# Boris_IO_3.net
KiCad netlist of a schematic drawn in Altium Designer
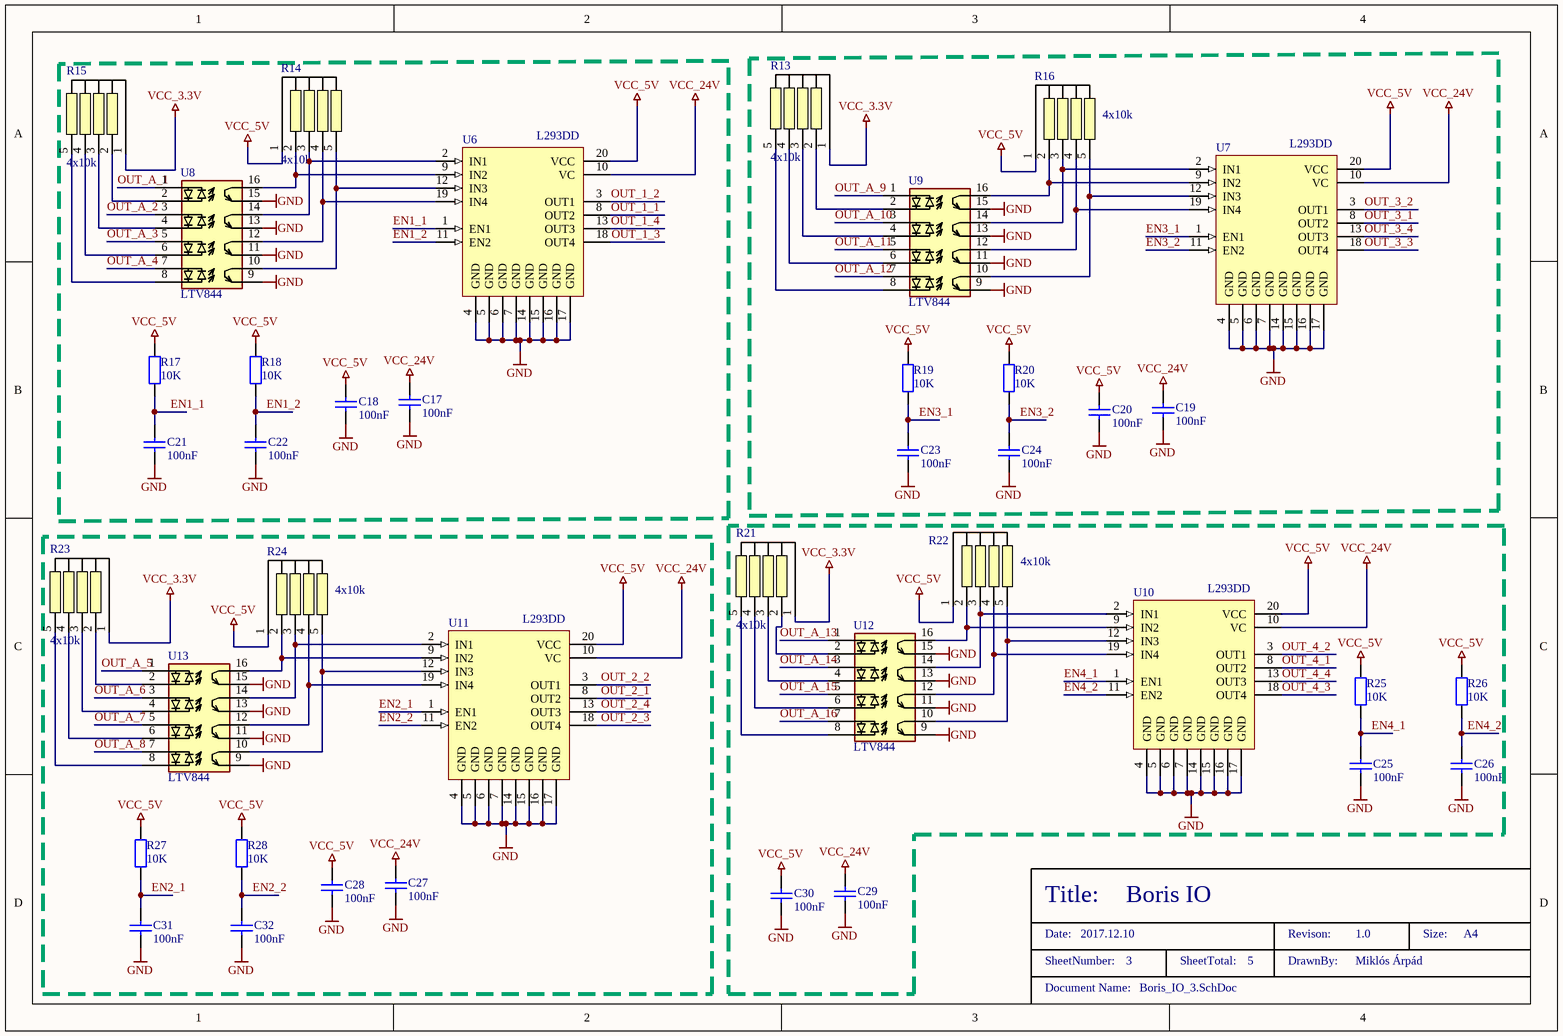
[diagram p0: Boris_IO_3.SchDoc]

(export (version "E")
  (design (tool "Eeschema 10.0.6"))
  (components
    (comp (ref "C17")
      (value "100nF")
      (footprint "0805_CAP")
      (description "Capacitor")
      (libsource (lib "Miscellaneous Devices") (part "Cap"))
    )
    (comp (ref "C18")
      (value "100nF")
      (footprint "0805_CAP")
      (description "Capacitor")
      (libsource (lib "Miscellaneous Devices") (part "Cap"))
    )
    (comp (ref "C19")
      (value "100nF")
      (footprint "0805_CAP")
      (description "Capacitor")
      (libsource (lib "Miscellaneous Devices") (part "Cap"))
    )
    (comp (ref "C20")
      (value "100nF")
      (footprint "0805_CAP")
      (description "Capacitor")
      (libsource (lib "Miscellaneous Devices") (part "Cap"))
    )
    (comp (ref "C21")
      (value "100nF")
      (footprint "0805_CAP")
      (description "Capacitor")
      (libsource (lib "Miscellaneous Devices") (part "Cap"))
    )
    (comp (ref "C22")
      (value "100nF")
      (footprint "0805_CAP")
      (description "Capacitor")
      (libsource (lib "Miscellaneous Devices") (part "Cap"))
    )
    (comp (ref "C23")
      (value "100nF")
      (footprint "0805_CAP")
      (description "Capacitor")
      (libsource (lib "Miscellaneous Devices") (part "Cap"))
    )
    (comp (ref "C24")
      (value "100nF")
      (footprint "0805_CAP")
      (description "Capacitor")
      (libsource (lib "Miscellaneous Devices") (part "Cap"))
    )
    (comp (ref "C25")
      (value "100nF")
      (footprint "0805_CAP")
      (description "Capacitor")
      (libsource (lib "Miscellaneous Devices") (part "Cap"))
    )
    (comp (ref "C26")
      (value "100nF")
      (footprint "0805_CAP")
      (description "Capacitor")
      (libsource (lib "Miscellaneous Devices") (part "Cap"))
    )
    (comp (ref "C27")
      (value "100nF")
      (footprint "0805_CAP")
      (description "Capacitor")
      (libsource (lib "Miscellaneous Devices") (part "Cap"))
    )
    (comp (ref "C28")
      (value "100nF")
      (footprint "0805_CAP")
      (description "Capacitor")
      (libsource (lib "Miscellaneous Devices") (part "Cap"))
    )
    (comp (ref "C29")
      (value "100nF")
      (footprint "0805_CAP")
      (description "Capacitor")
      (libsource (lib "Miscellaneous Devices") (part "Cap"))
    )
    (comp (ref "C30")
      (value "100nF")
      (footprint "0805_CAP")
      (description "Capacitor")
      (libsource (lib "Miscellaneous Devices") (part "Cap"))
    )
    (comp (ref "C31")
      (value "100nF")
      (footprint "0805_CAP")
      (description "Capacitor")
      (libsource (lib "Miscellaneous Devices") (part "Cap"))
    )
    (comp (ref "C32")
      (value "100nF")
      (footprint "0805_CAP")
      (description "Capacitor")
      (libsource (lib "Miscellaneous Devices") (part "Cap"))
    )
    (comp (ref "R13") (value "4x10k") (footprint "NFD_SIL-RES-5") (libsource (lib "") (part "SIL_10k_1")))
    (comp (ref "R14") (value "4x10k") (footprint "NFD_SIL-RES-5") (libsource (lib "IO-01") (part "SIL_10k")))
    (comp (ref "R15") (value "4x10k") (footprint "NFD_SIL-RES-5") (libsource (lib "") (part "SIL_10k_1")))
    (comp (ref "R16") (value "4x10k") (footprint "NFD_SIL-RES-5") (libsource (lib "IO-01") (part "SIL_10k")))
    (comp (ref "R17")
      (value "10K")
      (footprint "0805_RES")
      (description "Resistor")
      (libsource (lib "Miscellaneous Devices") (part "Res2"))
    )
    (comp (ref "R18")
      (value "10K")
      (footprint "0805_RES")
      (description "Resistor")
      (libsource (lib "Miscellaneous Devices") (part "Res2"))
    )
    (comp (ref "R19")
      (value "10K")
      (footprint "0805_RES")
      (description "Resistor")
      (libsource (lib "Miscellaneous Devices") (part "Res2"))
    )
    (comp (ref "R20")
      (value "10K")
      (footprint "0805_RES")
      (description "Resistor")
      (libsource (lib "Miscellaneous Devices") (part "Res2"))
    )
    (comp (ref "R21") (value "4x10k") (footprint "NFD_SIL-RES-5") (libsource (lib "") (part "SIL_10k_1")))
    (comp (ref "R22") (value "4x10k") (footprint "NFD_SIL-RES-5") (libsource (lib "IO-01") (part "SIL_10k")))
    (comp (ref "R23") (value "4x10k") (footprint "NFD_SIL-RES-5") (libsource (lib "") (part "SIL_10k_1")))
    (comp (ref "R24") (value "4x10k") (footprint "NFD_SIL-RES-5") (libsource (lib "IO-01") (part "SIL_10k")))
    (comp (ref "R25")
      (value "10K")
      (footprint "0805_RES")
      (description "Resistor")
      (libsource (lib "Miscellaneous Devices") (part "Res2"))
    )
    (comp (ref "R26")
      (value "10K")
      (footprint "0805_RES")
      (description "Resistor")
      (libsource (lib "Miscellaneous Devices") (part "Res2"))
    )
    (comp (ref "R27")
      (value "10K")
      (footprint "0805_RES")
      (description "Resistor")
      (libsource (lib "Miscellaneous Devices") (part "Res2"))
    )
    (comp (ref "R28")
      (value "10K")
      (footprint "0805_RES")
      (description "Resistor")
      (libsource (lib "Miscellaneous Devices") (part "Res2"))
    )
    (comp (ref "U6")
      (value "L293DD")
      (footprint "SO20_N")
      (description "Push-Pull Four Channel Driver With Diode")
      (fields (field (name "PUBLISHER") "Altium Limited"))
      (libsource (lib "ST Interface DC & Stepper Motor Controller") (part "L293DD"))
    )
    (comp (ref "U7")
      (value "L293DD")
      (footprint "SO20_N")
      (description "Push-Pull Four Channel Driver With Diode")
      (fields (field (name "PUBLISHER") "Altium Limited"))
      (libsource (lib "ST Interface DC & Stepper Motor Controller") (part "L293DD"))
    )
    (comp (ref "U8")
      (value "LTV844")
      (footprint "LTV844S")
      (description "4x optocoupler")
      (libsource (lib "MisiIC1") (part "LTV844"))
    )
    (comp (ref "U9")
      (value "LTV844")
      (footprint "LTV844S")
      (description "4x optocoupler")
      (libsource (lib "MisiIC1") (part "LTV844"))
    )
    (comp (ref "U10")
      (value "L293DD")
      (footprint "SO20_N")
      (description "Push-Pull Four Channel Driver With Diode")
      (fields (field (name "PUBLISHER") "Altium Limited"))
      (libsource (lib "ST Interface DC & Stepper Motor Controller") (part "L293DD"))
    )
    (comp (ref "U11")
      (value "L293DD")
      (footprint "SO20_N")
      (description "Push-Pull Four Channel Driver With Diode")
      (fields (field (name "PUBLISHER") "Altium Limited"))
      (libsource (lib "ST Interface DC & Stepper Motor Controller") (part "L293DD"))
    )
    (comp (ref "U12")
      (value "LTV844")
      (footprint "LTV844S")
      (description "4x optocoupler")
      (libsource (lib "MisiIC1") (part "LTV844"))
    )
    (comp (ref "U13")
      (value "LTV844")
      (footprint "LTV844S")
      (description "4x optocoupler")
      (libsource (lib "MisiIC1") (part "LTV844"))
    )
  )
  (nets
    (net (code "1") (name "/EN1_1") (class "Default")
      (node (ref "C21") (pin "1") (pinfunction "1_1") (pintype "passive"))
      (node (ref "R17") (pin "1") (pinfunction "1_1") (pintype "passive"))
      (node (ref "U6") (pin "1") (pinfunction "EN1_1") (pintype "input"))
    )
    (net (code "2") (name "/EN1_2") (class "Default")
      (node (ref "C22") (pin "1") (pinfunction "1_1") (pintype "passive"))
      (node (ref "R18") (pin "1") (pinfunction "1_1") (pintype "passive"))
      (node (ref "U6") (pin "11") (pinfunction "EN2_11") (pintype "input"))
    )
    (net (code "3") (name "/EN2_1") (class "Default")
      (node (ref "C31") (pin "1") (pinfunction "1_1") (pintype "passive"))
      (node (ref "R27") (pin "1") (pinfunction "1_1") (pintype "passive"))
      (node (ref "U11") (pin "1") (pinfunction "EN1_1") (pintype "input"))
    )
    (net (code "4") (name "/EN2_2") (class "Default")
      (node (ref "C32") (pin "1") (pinfunction "1_1") (pintype "passive"))
      (node (ref "R28") (pin "1") (pinfunction "1_1") (pintype "passive"))
      (node (ref "U11") (pin "11") (pinfunction "EN2_11") (pintype "input"))
    )
    (net (code "5") (name "/EN3_1") (class "Default")
      (node (ref "C23") (pin "1") (pinfunction "1_1") (pintype "passive"))
      (node (ref "R19") (pin "1") (pinfunction "1_1") (pintype "passive"))
      (node (ref "U7") (pin "1") (pinfunction "EN1_1") (pintype "input"))
    )
    (net (code "6") (name "/EN3_2") (class "Default")
      (node (ref "C24") (pin "1") (pinfunction "1_1") (pintype "passive"))
      (node (ref "R20") (pin "1") (pinfunction "1_1") (pintype "passive"))
      (node (ref "U7") (pin "11") (pinfunction "EN2_11") (pintype "input"))
    )
    (net (code "7") (name "/EN4_1") (class "Default")
      (node (ref "C25") (pin "1") (pinfunction "1_1") (pintype "passive"))
      (node (ref "R25") (pin "1") (pinfunction "1_1") (pintype "passive"))
      (node (ref "U10") (pin "1") (pinfunction "EN1_1") (pintype "input"))
    )
    (net (code "8") (name "/EN4_2") (class "Default")
      (node (ref "C26") (pin "1") (pinfunction "1_1") (pintype "passive"))
      (node (ref "R26") (pin "1") (pinfunction "1_1") (pintype "passive"))
      (node (ref "U10") (pin "11") (pinfunction "EN2_11") (pintype "input"))
    )
    (net (code "9") (name "/OUT_1_1") (class "Default")
      (node (ref "U6") (pin "8") (pinfunction "OUT2_8") (pintype "tri_state"))
    )
    (net (code "10") (name "/OUT_1_2") (class "Default")
      (node (ref "U6") (pin "3") (pinfunction "OUT1_3") (pintype "tri_state"))
    )
    (net (code "11") (name "/OUT_1_3") (class "Default")
      (node (ref "U6") (pin "18") (pinfunction "OUT4_18") (pintype "tri_state"))
    )
    (net (code "12") (name "/OUT_1_4") (class "Default")
      (node (ref "U6") (pin "13") (pinfunction "OUT3_13") (pintype "tri_state"))
    )
    (net (code "13") (name "/OUT_2_1") (class "Default")
      (node (ref "U11") (pin "8") (pinfunction "OUT2_8") (pintype "tri_state"))
    )
    (net (code "14") (name "/OUT_2_2") (class "Default")
      (node (ref "U11") (pin "3") (pinfunction "OUT1_3") (pintype "tri_state"))
    )
    (net (code "15") (name "/OUT_2_3") (class "Default")
      (node (ref "U11") (pin "18") (pinfunction "OUT4_18") (pintype "tri_state"))
    )
    (net (code "16") (name "/OUT_2_4") (class "Default")
      (node (ref "U11") (pin "13") (pinfunction "OUT3_13") (pintype "tri_state"))
    )
    (net (code "17") (name "/OUT_3_1") (class "Default")
      (node (ref "U7") (pin "8") (pinfunction "OUT2_8") (pintype "tri_state"))
    )
    (net (code "18") (name "/OUT_3_2") (class "Default")
      (node (ref "U7") (pin "3") (pinfunction "OUT1_3") (pintype "tri_state"))
    )
    (net (code "19") (name "/OUT_3_3") (class "Default")
      (node (ref "U7") (pin "18") (pinfunction "OUT4_18") (pintype "tri_state"))
    )
    (net (code "20") (name "/OUT_3_4") (class "Default")
      (node (ref "U7") (pin "13") (pinfunction "OUT3_13") (pintype "tri_state"))
    )
    (net (code "21") (name "/OUT_4_1") (class "Default")
      (node (ref "U10") (pin "8") (pinfunction "OUT2_8") (pintype "tri_state"))
    )
    (net (code "22") (name "/OUT_4_2") (class "Default")
      (node (ref "U10") (pin "3") (pinfunction "OUT1_3") (pintype "tri_state"))
    )
    (net (code "23") (name "/OUT_4_3") (class "Default")
      (node (ref "U10") (pin "18") (pinfunction "OUT4_18") (pintype "tri_state"))
    )
    (net (code "24") (name "/OUT_4_4") (class "Default")
      (node (ref "U10") (pin "13") (pinfunction "OUT3_13") (pintype "tri_state"))
    )
    (net (code "25") (name "/OUT_A_1") (class "Default")
      (node (ref "U8") (pin "1") (pinfunction "1_1") (pintype "passive"))
    )
    (net (code "26") (name "/OUT_A_2") (class "Default")
      (node (ref "U8") (pin "3") (pinfunction "3_3") (pintype "passive"))
    )
    (net (code "27") (name "/OUT_A_3") (class "Default")
      (node (ref "U8") (pin "5") (pinfunction "5_5") (pintype "passive"))
    )
    (net (code "28") (name "/OUT_A_4") (class "Default")
      (node (ref "U8") (pin "7") (pinfunction "7_7") (pintype "passive"))
    )
    (net (code "29") (name "/OUT_A_5") (class "Default")
      (node (ref "U13") (pin "1") (pinfunction "1_1") (pintype "passive"))
    )
    (net (code "30") (name "/OUT_A_6") (class "Default")
      (node (ref "U13") (pin "3") (pinfunction "3_3") (pintype "passive"))
    )
    (net (code "31") (name "/OUT_A_7") (class "Default")
      (node (ref "U13") (pin "5") (pinfunction "5_5") (pintype "passive"))
    )
    (net (code "32") (name "/OUT_A_8") (class "Default")
      (node (ref "U13") (pin "7") (pinfunction "7_7") (pintype "passive"))
    )
    (net (code "33") (name "/OUT_A_9") (class "Default")
      (node (ref "U9") (pin "1") (pinfunction "1_1") (pintype "passive"))
    )
    (net (code "34") (name "/OUT_A_10") (class "Default")
      (node (ref "U9") (pin "3") (pinfunction "3_3") (pintype "passive"))
    )
    (net (code "35") (name "/OUT_A_11") (class "Default")
      (node (ref "U9") (pin "5") (pinfunction "5_5") (pintype "passive"))
    )
    (net (code "36") (name "/OUT_A_12") (class "Default")
      (node (ref "U9") (pin "7") (pinfunction "7_7") (pintype "passive"))
    )
    (net (code "37") (name "/OUT_A_13") (class "Default")
      (node (ref "U12") (pin "1") (pinfunction "1_1") (pintype "passive"))
    )
    (net (code "38") (name "/OUT_A_14") (class "Default")
      (node (ref "U12") (pin "3") (pinfunction "3_3") (pintype "passive"))
    )
    (net (code "39") (name "/OUT_A_15") (class "Default")
      (node (ref "U12") (pin "5") (pinfunction "5_5") (pintype "passive"))
    )
    (net (code "40") (name "/OUT_A_16") (class "Default")
      (node (ref "U12") (pin "7") (pinfunction "7_7") (pintype "passive"))
    )
    (net (code "41") (name "GND") (class "Default")
      (node (ref "C17") (pin "2") (pinfunction "2_2") (pintype "passive"))
      (node (ref "C18") (pin "2") (pinfunction "2_2") (pintype "passive"))
      (node (ref "C19") (pin "2") (pinfunction "2_2") (pintype "passive"))
      (node (ref "C20") (pin "2") (pinfunction "2_2") (pintype "passive"))
      (node (ref "C21") (pin "2") (pinfunction "2_2") (pintype "passive"))
      (node (ref "C22") (pin "2") (pinfunction "2_2") (pintype "passive"))
      (node (ref "C23") (pin "2") (pinfunction "2_2") (pintype "passive"))
      (node (ref "C24") (pin "2") (pinfunction "2_2") (pintype "passive"))
      (node (ref "C25") (pin "2") (pinfunction "2_2") (pintype "passive"))
      (node (ref "C26") (pin "2") (pinfunction "2_2") (pintype "passive"))
      (node (ref "C27") (pin "2") (pinfunction "2_2") (pintype "passive"))
      (node (ref "C28") (pin "2") (pinfunction "2_2") (pintype "passive"))
      (node (ref "C29") (pin "2") (pinfunction "2_2") (pintype "passive"))
      (node (ref "C30") (pin "2") (pinfunction "2_2") (pintype "passive"))
      (node (ref "C31") (pin "2") (pinfunction "2_2") (pintype "passive"))
      (node (ref "C32") (pin "2") (pinfunction "2_2") (pintype "passive"))
      (node (ref "U10") (pin "14") (pinfunction "GND_14") (pintype "power_in"))
      (node (ref "U10") (pin "15") (pinfunction "GND_15") (pintype "power_in"))
      (node (ref "U10") (pin "16") (pinfunction "GND_16") (pintype "power_in"))
      (node (ref "U10") (pin "17") (pinfunction "GND_17") (pintype "power_in"))
      (node (ref "U10") (pin "4") (pinfunction "GND_4") (pintype "power_in"))
      (node (ref "U10") (pin "5") (pinfunction "GND_5") (pintype "power_in"))
      (node (ref "U10") (pin "6") (pinfunction "GND_6") (pintype "power_in"))
      (node (ref "U10") (pin "7") (pinfunction "GND_7") (pintype "power_in"))
      (node (ref "U11") (pin "14") (pinfunction "GND_14") (pintype "power_in"))
      (node (ref "U11") (pin "15") (pinfunction "GND_15") (pintype "power_in"))
      (node (ref "U11") (pin "16") (pinfunction "GND_16") (pintype "power_in"))
      (node (ref "U11") (pin "17") (pinfunction "GND_17") (pintype "power_in"))
      (node (ref "U11") (pin "4") (pinfunction "GND_4") (pintype "power_in"))
      (node (ref "U11") (pin "5") (pinfunction "GND_5") (pintype "power_in"))
      (node (ref "U11") (pin "6") (pinfunction "GND_6") (pintype "power_in"))
      (node (ref "U11") (pin "7") (pinfunction "GND_7") (pintype "power_in"))
      (node (ref "U12") (pin "11") (pinfunction "11_11") (pintype "passive"))
      (node (ref "U12") (pin "13") (pinfunction "13_13") (pintype "passive"))
      (node (ref "U12") (pin "15") (pinfunction "15_15") (pintype "passive"))
      (node (ref "U12") (pin "9") (pinfunction "9_9") (pintype "passive"))
      (node (ref "U13") (pin "11") (pinfunction "11_11") (pintype "passive"))
      (node (ref "U13") (pin "13") (pinfunction "13_13") (pintype "passive"))
      (node (ref "U13") (pin "15") (pinfunction "15_15") (pintype "passive"))
      (node (ref "U13") (pin "9") (pinfunction "9_9") (pintype "passive"))
      (node (ref "U6") (pin "14") (pinfunction "GND_14") (pintype "power_in"))
      (node (ref "U6") (pin "15") (pinfunction "GND_15") (pintype "power_in"))
      (node (ref "U6") (pin "16") (pinfunction "GND_16") (pintype "power_in"))
      (node (ref "U6") (pin "17") (pinfunction "GND_17") (pintype "power_in"))
      (node (ref "U6") (pin "4") (pinfunction "GND_4") (pintype "power_in"))
      (node (ref "U6") (pin "5") (pinfunction "GND_5") (pintype "power_in"))
      (node (ref "U6") (pin "6") (pinfunction "GND_6") (pintype "power_in"))
      (node (ref "U6") (pin "7") (pinfunction "GND_7") (pintype "power_in"))
      (node (ref "U7") (pin "14") (pinfunction "GND_14") (pintype "power_in"))
      (node (ref "U7") (pin "15") (pinfunction "GND_15") (pintype "power_in"))
      (node (ref "U7") (pin "16") (pinfunction "GND_16") (pintype "power_in"))
      (node (ref "U7") (pin "17") (pinfunction "GND_17") (pintype "power_in"))
      (node (ref "U7") (pin "4") (pinfunction "GND_4") (pintype "power_in"))
      (node (ref "U7") (pin "5") (pinfunction "GND_5") (pintype "power_in"))
      (node (ref "U7") (pin "6") (pinfunction "GND_6") (pintype "power_in"))
      (node (ref "U7") (pin "7") (pinfunction "GND_7") (pintype "power_in"))
      (node (ref "U8") (pin "11") (pinfunction "11_11") (pintype "passive"))
      (node (ref "U8") (pin "13") (pinfunction "13_13") (pintype "passive"))
      (node (ref "U8") (pin "15") (pinfunction "15_15") (pintype "passive"))
      (node (ref "U8") (pin "9") (pinfunction "9_9") (pintype "passive"))
      (node (ref "U9") (pin "11") (pinfunction "11_11") (pintype "passive"))
      (node (ref "U9") (pin "13") (pinfunction "13_13") (pintype "passive"))
      (node (ref "U9") (pin "15") (pinfunction "15_15") (pintype "passive"))
      (node (ref "U9") (pin "9") (pinfunction "9_9") (pintype "passive"))
    )
    (net (code "42") (name "Net-(R13-Pad2)") (class "Default")
      (node (ref "R13") (pin "2") (pinfunction "2_2") (pintype "passive"))
      (node (ref "U9") (pin "2") (pinfunction "2_2") (pintype "passive"))
    )
    (net (code "43") (name "Net-(R13-Pad3)") (class "Default")
      (node (ref "R13") (pin "3") (pinfunction "3_3") (pintype "passive"))
      (node (ref "U9") (pin "4") (pinfunction "4_4") (pintype "passive"))
    )
    (net (code "44") (name "Net-(R13-Pad4)") (class "Default")
      (node (ref "R13") (pin "4") (pinfunction "4_4") (pintype "passive"))
      (node (ref "U9") (pin "6") (pinfunction "6_6") (pintype "passive"))
    )
    (net (code "45") (name "Net-(R13-Pad5)") (class "Default")
      (node (ref "R13") (pin "5") (pinfunction "5_5") (pintype "passive"))
      (node (ref "U9") (pin "8") (pinfunction "8_8") (pintype "passive"))
    )
    (net (code "46") (name "Net-(R15-Pad2)") (class "Default")
      (node (ref "R15") (pin "2") (pinfunction "2_2") (pintype "passive"))
      (node (ref "U8") (pin "2") (pinfunction "2_2") (pintype "passive"))
    )
    (net (code "47") (name "Net-(R15-Pad3)") (class "Default")
      (node (ref "R15") (pin "3") (pinfunction "3_3") (pintype "passive"))
      (node (ref "U8") (pin "4") (pinfunction "4_4") (pintype "passive"))
    )
    (net (code "48") (name "Net-(R15-Pad4)") (class "Default")
      (node (ref "R15") (pin "4") (pinfunction "4_4") (pintype "passive"))
      (node (ref "U8") (pin "6") (pinfunction "6_6") (pintype "passive"))
    )
    (net (code "49") (name "Net-(R15-Pad5)") (class "Default")
      (node (ref "R15") (pin "5") (pinfunction "5_5") (pintype "passive"))
      (node (ref "U8") (pin "8") (pinfunction "8_8") (pintype "passive"))
    )
    (net (code "50") (name "Net-(R21-Pad2)") (class "Default")
      (node (ref "R21") (pin "2") (pinfunction "2_2") (pintype "passive"))
      (node (ref "U12") (pin "2") (pinfunction "2_2") (pintype "passive"))
    )
    (net (code "51") (name "Net-(R21-Pad3)") (class "Default")
      (node (ref "R21") (pin "3") (pinfunction "3_3") (pintype "passive"))
      (node (ref "U12") (pin "4") (pinfunction "4_4") (pintype "passive"))
    )
    (net (code "52") (name "Net-(R21-Pad4)") (class "Default")
      (node (ref "R21") (pin "4") (pinfunction "4_4") (pintype "passive"))
      (node (ref "U12") (pin "6") (pinfunction "6_6") (pintype "passive"))
    )
    (net (code "53") (name "Net-(R21-Pad5)") (class "Default")
      (node (ref "R21") (pin "5") (pinfunction "5_5") (pintype "passive"))
      (node (ref "U12") (pin "8") (pinfunction "8_8") (pintype "passive"))
    )
    (net (code "54") (name "Net-(R23-Pad2)") (class "Default")
      (node (ref "R23") (pin "2") (pinfunction "2_2") (pintype "passive"))
      (node (ref "U13") (pin "2") (pinfunction "2_2") (pintype "passive"))
    )
    (net (code "55") (name "Net-(R23-Pad3)") (class "Default")
      (node (ref "R23") (pin "3") (pinfunction "3_3") (pintype "passive"))
      (node (ref "U13") (pin "4") (pinfunction "4_4") (pintype "passive"))
    )
    (net (code "56") (name "Net-(R23-Pad4)") (class "Default")
      (node (ref "R23") (pin "4") (pinfunction "4_4") (pintype "passive"))
      (node (ref "U13") (pin "6") (pinfunction "6_6") (pintype "passive"))
    )
    (net (code "57") (name "Net-(R23-Pad5)") (class "Default")
      (node (ref "R23") (pin "5") (pinfunction "5_5") (pintype "passive"))
      (node (ref "U13") (pin "8") (pinfunction "8_8") (pintype "passive"))
    )
    (net (code "58") (name "Net-(U6-IN1)") (class "Default")
      (node (ref "R14") (pin "3") (pinfunction "3_3") (pintype "passive"))
      (node (ref "U6") (pin "2") (pinfunction "IN1_2") (pintype "input"))
      (node (ref "U8") (pin "14") (pinfunction "14_14") (pintype "passive"))
    )
    (net (code "59") (name "Net-(U6-IN2)") (class "Default")
      (node (ref "R14") (pin "2") (pinfunction "2_2") (pintype "passive"))
      (node (ref "U6") (pin "9") (pinfunction "IN2_9") (pintype "input"))
      (node (ref "U8") (pin "16") (pinfunction "16_16") (pintype "passive"))
    )
    (net (code "60") (name "Net-(U6-IN3)") (class "Default")
      (node (ref "R14") (pin "5") (pinfunction "5_5") (pintype "passive"))
      (node (ref "U6") (pin "12") (pinfunction "IN3_12") (pintype "input"))
      (node (ref "U8") (pin "10") (pinfunction "10_10") (pintype "passive"))
    )
    (net (code "61") (name "Net-(U6-IN4)") (class "Default")
      (node (ref "R14") (pin "4") (pinfunction "4_4") (pintype "passive"))
      (node (ref "U6") (pin "19") (pinfunction "IN4_19") (pintype "input"))
      (node (ref "U8") (pin "12") (pinfunction "12_12") (pintype "passive"))
    )
    (net (code "62") (name "Net-(U7-IN1)") (class "Default")
      (node (ref "R16") (pin "3") (pinfunction "3_3") (pintype "passive"))
      (node (ref "U7") (pin "2") (pinfunction "IN1_2") (pintype "input"))
      (node (ref "U9") (pin "14") (pinfunction "14_14") (pintype "passive"))
    )
    (net (code "63") (name "Net-(U7-IN2)") (class "Default")
      (node (ref "R16") (pin "2") (pinfunction "2_2") (pintype "passive"))
      (node (ref "U7") (pin "9") (pinfunction "IN2_9") (pintype "input"))
      (node (ref "U9") (pin "16") (pinfunction "16_16") (pintype "passive"))
    )
    (net (code "64") (name "Net-(U7-IN3)") (class "Default")
      (node (ref "R16") (pin "5") (pinfunction "5_5") (pintype "passive"))
      (node (ref "U7") (pin "12") (pinfunction "IN3_12") (pintype "input"))
      (node (ref "U9") (pin "10") (pinfunction "10_10") (pintype "passive"))
    )
    (net (code "65") (name "Net-(U7-IN4)") (class "Default")
      (node (ref "R16") (pin "4") (pinfunction "4_4") (pintype "passive"))
      (node (ref "U7") (pin "19") (pinfunction "IN4_19") (pintype "input"))
      (node (ref "U9") (pin "12") (pinfunction "12_12") (pintype "passive"))
    )
    (net (code "66") (name "Net-(U10-IN1)") (class "Default")
      (node (ref "R22") (pin "3") (pinfunction "3_3") (pintype "passive"))
      (node (ref "U10") (pin "2") (pinfunction "IN1_2") (pintype "input"))
      (node (ref "U12") (pin "14") (pinfunction "14_14") (pintype "passive"))
    )
    (net (code "67") (name "Net-(U10-IN2)") (class "Default")
      (node (ref "R22") (pin "2") (pinfunction "2_2") (pintype "passive"))
      (node (ref "U10") (pin "9") (pinfunction "IN2_9") (pintype "input"))
      (node (ref "U12") (pin "16") (pinfunction "16_16") (pintype "passive"))
    )
    (net (code "68") (name "Net-(U10-IN3)") (class "Default")
      (node (ref "R22") (pin "5") (pinfunction "5_5") (pintype "passive"))
      (node (ref "U10") (pin "12") (pinfunction "IN3_12") (pintype "input"))
      (node (ref "U12") (pin "10") (pinfunction "10_10") (pintype "passive"))
    )
    (net (code "69") (name "Net-(U10-IN4)") (class "Default")
      (node (ref "R22") (pin "4") (pinfunction "4_4") (pintype "passive"))
      (node (ref "U10") (pin "19") (pinfunction "IN4_19") (pintype "input"))
      (node (ref "U12") (pin "12") (pinfunction "12_12") (pintype "passive"))
    )
    (net (code "70") (name "Net-(U11-IN1)") (class "Default")
      (node (ref "R24") (pin "3") (pinfunction "3_3") (pintype "passive"))
      (node (ref "U11") (pin "2") (pinfunction "IN1_2") (pintype "input"))
      (node (ref "U13") (pin "14") (pinfunction "14_14") (pintype "passive"))
    )
    (net (code "71") (name "Net-(U11-IN2)") (class "Default")
      (node (ref "R24") (pin "2") (pinfunction "2_2") (pintype "passive"))
      (node (ref "U11") (pin "9") (pinfunction "IN2_9") (pintype "input"))
      (node (ref "U13") (pin "16") (pinfunction "16_16") (pintype "passive"))
    )
    (net (code "72") (name "Net-(U11-IN3)") (class "Default")
      (node (ref "R24") (pin "5") (pinfunction "5_5") (pintype "passive"))
      (node (ref "U11") (pin "12") (pinfunction "IN3_12") (pintype "input"))
      (node (ref "U13") (pin "10") (pinfunction "10_10") (pintype "passive"))
    )
    (net (code "73") (name "Net-(U11-IN4)") (class "Default")
      (node (ref "R24") (pin "4") (pinfunction "4_4") (pintype "passive"))
      (node (ref "U11") (pin "19") (pinfunction "IN4_19") (pintype "input"))
      (node (ref "U13") (pin "12") (pinfunction "12_12") (pintype "passive"))
    )
    (net (code "74") (name "VCC_3.3V") (class "Default")
      (node (ref "R13") (pin "1") (pinfunction "1_1") (pintype "passive"))
      (node (ref "R15") (pin "1") (pinfunction "1_1") (pintype "passive"))
      (node (ref "R21") (pin "1") (pinfunction "1_1") (pintype "passive"))
      (node (ref "R23") (pin "1") (pinfunction "1_1") (pintype "passive"))
    )
    (net (code "75") (name "VCC_5V") (class "Default")
      (node (ref "C18") (pin "1") (pinfunction "1_1") (pintype "passive"))
      (node (ref "C20") (pin "1") (pinfunction "1_1") (pintype "passive"))
      (node (ref "C28") (pin "1") (pinfunction "1_1") (pintype "passive"))
      (node (ref "C30") (pin "1") (pinfunction "1_1") (pintype "passive"))
      (node (ref "R14") (pin "1") (pinfunction "1_1") (pintype "passive"))
      (node (ref "R16") (pin "1") (pinfunction "1_1") (pintype "passive"))
      (node (ref "R17") (pin "2") (pinfunction "2_2") (pintype "passive"))
      (node (ref "R18") (pin "2") (pinfunction "2_2") (pintype "passive"))
      (node (ref "R19") (pin "2") (pinfunction "2_2") (pintype "passive"))
      (node (ref "R20") (pin "2") (pinfunction "2_2") (pintype "passive"))
      (node (ref "R22") (pin "1") (pinfunction "1_1") (pintype "passive"))
      (node (ref "R24") (pin "1") (pinfunction "1_1") (pintype "passive"))
      (node (ref "R25") (pin "2") (pinfunction "2_2") (pintype "passive"))
      (node (ref "R26") (pin "2") (pinfunction "2_2") (pintype "passive"))
      (node (ref "R27") (pin "2") (pinfunction "2_2") (pintype "passive"))
      (node (ref "R28") (pin "2") (pinfunction "2_2") (pintype "passive"))
      (node (ref "U10") (pin "20") (pinfunction "VCC_20") (pintype "power_in"))
      (node (ref "U11") (pin "20") (pinfunction "VCC_20") (pintype "power_in"))
      (node (ref "U6") (pin "20") (pinfunction "VCC_20") (pintype "power_in"))
      (node (ref "U7") (pin "20") (pinfunction "VCC_20") (pintype "power_in"))
    )
    (net (code "76") (name "VCC_24V") (class "Default")
      (node (ref "C17") (pin "1") (pinfunction "1_1") (pintype "passive"))
      (node (ref "C19") (pin "1") (pinfunction "1_1") (pintype "passive"))
      (node (ref "C27") (pin "1") (pinfunction "1_1") (pintype "passive"))
      (node (ref "C29") (pin "1") (pinfunction "1_1") (pintype "passive"))
      (node (ref "U10") (pin "10") (pinfunction "VC_10") (pintype "power_in"))
      (node (ref "U11") (pin "10") (pinfunction "VC_10") (pintype "power_in"))
      (node (ref "U6") (pin "10") (pinfunction "VC_10") (pintype "power_in"))
      (node (ref "U7") (pin "10") (pinfunction "VC_10") (pintype "power_in"))
    )
  )
)
